# 5VBuckConverterSM.net
KiCad netlist of a schematic drawn in Altium Designer
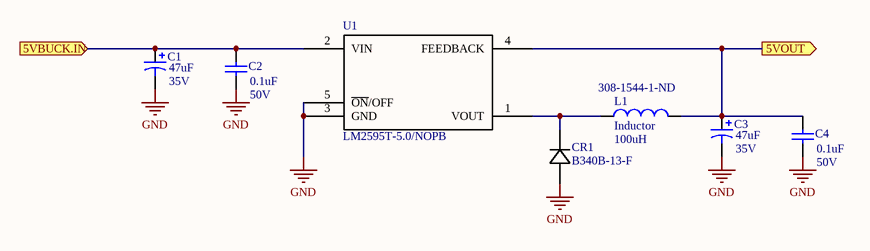
[diagram p0: 5VBuckConverterSM.SchDoc]

(export (version "E")
  (design (tool "Eeschema 10.0.6"))
  (components
    (comp (ref "C1")
      (value "47uF")
      (footprint "RB7.6-15")
      (description "Polarized Capacitor (Radial)")
      (fields
        (field (name "VOLTAGE RATING") "35V")
        (field (name "Comment") "Cap Pol1")
        (field (name "PUBLISHER") "Altium Limited")
      )
      (libsource (lib "Miscellaneous Devices") (part "Cap Pol1"))
    )
    (comp (ref "C2")
      (value "0.1uF")
      (footprint "RAD-0.3")
      (description "Capacitor")
      (fields
        (field (name "VOLTAGE RATING") "50V")
        (field (name "Comment") "Cap")
        (field (name "PUBLISHER") "Altium Limited")
      )
      (libsource (lib "Miscellaneous Devices") (part "Cap"))
    )
    (comp (ref "C3")
      (value "47uF")
      (footprint "RB7.6-15")
      (description "Polarized Capacitor (Radial)")
      (fields
        (field (name "VOLTAGE RATING") "35V")
        (field (name "Comment") "Cap Pol1")
        (field (name "PUBLISHER") "Altium Limited")
      )
      (libsource (lib "Miscellaneous Devices") (part "Cap Pol1"))
    )
    (comp (ref "C4")
      (value "0.1uF")
      (footprint "RAD-0.3")
      (description "Capacitor")
      (fields
        (field (name "VOLTAGE RATING") "50V")
        (field (name "Comment") "Cap")
        (field (name "PUBLISHER") "Altium Limited")
      )
      (libsource (lib "Miscellaneous Devices") (part "Cap"))
    )
    (comp (ref "CR1")
      (value "B340B-13-F")
      (footprint "B340A-13-F")
      (description "No Description Available")
      (fields (field (name "COPYRIGHT") "Copyright (C) 2022 Ultra Librarian. All rights reserved."))
      (libsource (lib "B340B-13-F") (part "B340B-13-F"))
    )
    (comp (ref "L1")
      (value "Inductor")
      (footprint "0402-A")
      (description "Ind Power Shielded Wirewound 100uH 20% 100KHz 1.6A Carrier T/R")
      (fields
        (field (name "ALTIUM_VALUE") "100uH")
        (field (name "SUPPLIER PART NUMBER 1") "308-1544-1-ND")
        (field (name "MANUFACTURER") "Sumida")
        (field (name "MANUFACTURER PART NUMBER") "CDRH125/LDNP-101MC")
        (field (name "PUBLISHER") "Altium Limited")
      )
      (libsource (lib "Miscellaneous Devices") (part "Inductor"))
    )
    (comp (ref "U1")
      (value "LM2595T-5.0/NOPB")
      (footprint "LM2595ST-5P0")
      (libsource (lib "Parts") (part "LM2595T-5.0/NOPB"))
    )
  )
  (nets
    (net (code "1") (name "/5VBUCK.IN") (class "Default")
      (node (ref "C1") (pin "1") (pinfunction "1_1") (pintype "passive"))
      (node (ref "C2") (pin "2") (pinfunction "2_2") (pintype "passive"))
      (node (ref "U1") (pin "2") (pinfunction "VIN_2") (pintype "passive"))
    )
    (net (code "2") (name "/5VOUT") (class "Default")
      (node (ref "C3") (pin "1") (pinfunction "1_1") (pintype "passive"))
      (node (ref "C4") (pin "2") (pinfunction "2_2") (pintype "passive"))
      (node (ref "L1") (pin "2") (pinfunction "2_2") (pintype "passive"))
      (node (ref "U1") (pin "4") (pinfunction "FEEDBACK_4") (pintype "passive"))
    )
    (net (code "3") (name "GND") (class "Default")
      (node (ref "C1") (pin "2") (pinfunction "2_2") (pintype "passive"))
      (node (ref "C2") (pin "1") (pinfunction "1_1") (pintype "passive"))
      (node (ref "C3") (pin "2") (pinfunction "2_2") (pintype "passive"))
      (node (ref "C4") (pin "1") (pinfunction "1_1") (pintype "passive"))
      (node (ref "CR1") (pin "2") (pinfunction "2_2") (pintype "passive"))
      (node (ref "U1") (pin "3") (pinfunction "GND_3") (pintype "passive"))
      (node (ref "U1") (pin "5") (pinfunction "~{ON}/OFF_5") (pintype "passive"))
    )
    (net (code "4") (name "Net-(U1-VOUT)") (class "Default")
      (node (ref "CR1") (pin "1") (pinfunction "1_1") (pintype "passive"))
      (node (ref "L1") (pin "1") (pinfunction "1_1") (pintype "passive"))
      (node (ref "U1") (pin "1") (pinfunction "VOUT_1") (pintype "passive"))
    )
  )
)
